# sensor_interface.net
KiCad netlist of a schematic drawn in EAGLE
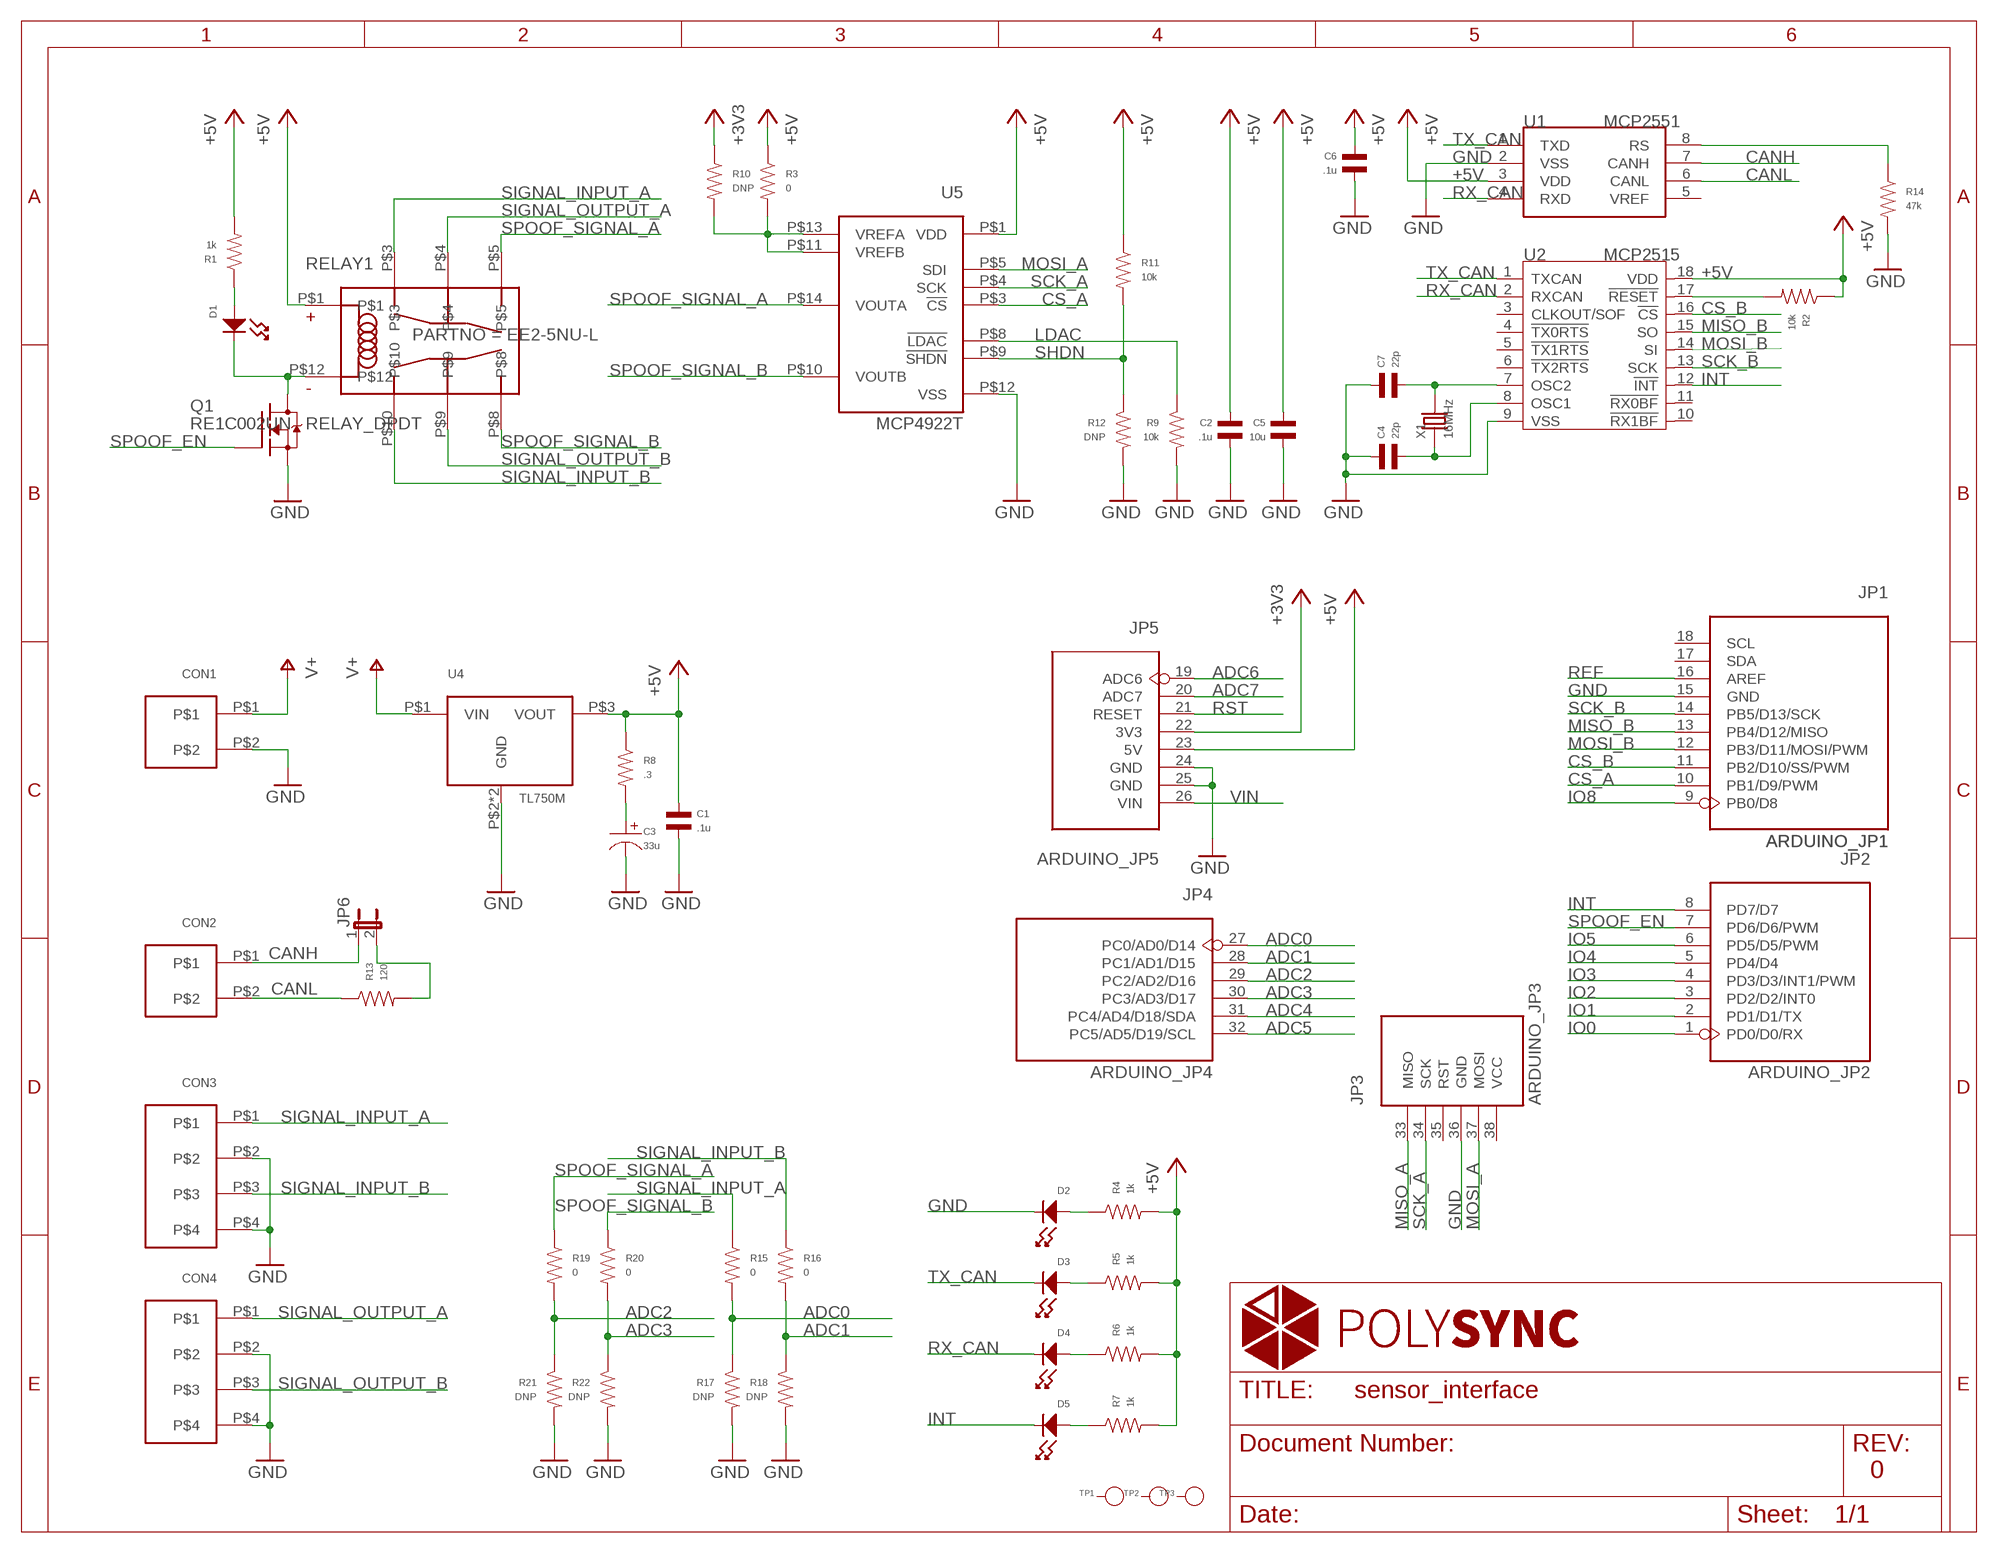
[diagram p0: schematic, sheet 1]

(export (version "E")
  (design (tool "Eeschema 10.0.6"))
  (components
    (comp (ref "C1")
      (value ".1u")
      (footprint "eagle-import:C0402")
      (libsource (lib "eagle-import") (part "CAPACITOR_NP_0402"))
    )
    (comp (ref "C2")
      (value ".1u")
      (footprint "eagle-import:C0402")
      (libsource (lib "eagle-import") (part "CAPACITOR_NP_0402"))
    )
    (comp (ref "C3")
      (value "33u")
      (footprint "eagle-import:CP1206")
      (libsource (lib "eagle-import") (part "CAPACITOR_P"))
    )
    (comp (ref "C4")
      (value "22p")
      (footprint "eagle-import:C0402")
      (libsource (lib "eagle-import") (part "CAPACITOR_NP_0402"))
    )
    (comp (ref "C5")
      (value "10u")
      (footprint "eagle-import:C0805")
      (libsource (lib "eagle-import") (part "CAPACITOR_NP_0805"))
    )
    (comp (ref "C6")
      (value ".1u")
      (footprint "eagle-import:C0402")
      (libsource (lib "eagle-import") (part "CAPACITOR_NP_0402"))
    )
    (comp (ref "C7")
      (value "22p")
      (footprint "eagle-import:C0402")
      (libsource (lib "eagle-import") (part "CAPACITOR_NP_0402"))
    )
    (comp (ref "CON1")
      (value "CON2")
      (footprint "eagle-import:PHOENIX_2_45")
      (libsource (lib "eagle-import") (part "CON2"))
    )
    (comp (ref "CON2")
      (value "CON2")
      (footprint "eagle-import:PHOENIX_2_45")
      (libsource (lib "eagle-import") (part "CON2"))
    )
    (comp (ref "CON3")
      (value "CON4")
      (footprint "eagle-import:PHOENIX_4_45")
      (libsource (lib "eagle-import") (part "CON4"))
    )
    (comp (ref "CON4")
      (value "CON4")
      (footprint "eagle-import:PHOENIX_4_45")
      (libsource (lib "eagle-import") (part "CON4"))
    )
    (comp (ref "D1")
      (value "LED_SINGLE-0603")
      (footprint "eagle-import:LED0603")
      (fields (field (name "HOUSEPART") "NO"))
      (libsource (lib "eagle-import") (part "LED_SINGLE-0603"))
    )
    (comp (ref "D2")
      (value "LED_SINGLE-0603")
      (footprint "eagle-import:LED0603")
      (fields (field (name "HOUSEPART") "NO"))
      (libsource (lib "eagle-import") (part "LED_SINGLE-0603"))
    )
    (comp (ref "D3")
      (value "LED_SINGLE-0603")
      (footprint "eagle-import:LED0603")
      (fields (field (name "HOUSEPART") "NO"))
      (libsource (lib "eagle-import") (part "LED_SINGLE-0603"))
    )
    (comp (ref "D4")
      (value "LED_SINGLE-0603")
      (footprint "eagle-import:LED0603")
      (fields (field (name "HOUSEPART") "NO"))
      (libsource (lib "eagle-import") (part "LED_SINGLE-0603"))
    )
    (comp (ref "D5")
      (value "LED_SINGLE-0603")
      (footprint "eagle-import:LED0603")
      (fields (field (name "HOUSEPART") "NO"))
      (libsource (lib "eagle-import") (part "LED_SINGLE-0603"))
    )
    (comp (ref "JP1")
      (value "ARDUINO_JP1")
      (footprint "eagle-import:ARDUINO_JP1")
      (libsource (lib "eagle-import") (part "ARDUINO_JP1"))
    )
    (comp (ref "JP2")
      (value "ARDUINO_JP2")
      (footprint "eagle-import:ARDUINO_JP2")
      (libsource (lib "eagle-import") (part "ARDUINO_JP2"))
    )
    (comp (ref "JP3")
      (value "ARDUINO_JP3")
      (footprint "eagle-import:ARDUINO_JP3")
      (libsource (lib "eagle-import") (part "ARDUINO_JP3"))
    )
    (comp (ref "JP4")
      (value "ARDUINO_JP4")
      (footprint "eagle-import:ARDUINO_JP4")
      (libsource (lib "eagle-import") (part "ARDUINO_JP4"))
    )
    (comp (ref "JP5")
      (value "ARDUINO_JP5")
      (footprint "eagle-import:ARDUINO_JP5")
      (libsource (lib "eagle-import") (part "ARDUINO_JP5"))
    )
    (comp (ref "JP6")
      (value "JP1E")
      (footprint "eagle-import:JP1")
      (libsource (lib "eagle-import") (part "JP1E"))
    )
    (comp (ref "Q1")
      (value "RE1C002UN")
      (footprint "eagle-import:EMT3F")
      (libsource (lib "eagle-import") (part "RE1C002UN"))
    )
    (comp (ref "R1")
      (value "1k")
      (footprint "eagle-import:R0402")
      (libsource (lib "eagle-import") (part "RESISTOR_0402"))
    )
    (comp (ref "R2")
      (value "10k")
      (footprint "eagle-import:R0402")
      (libsource (lib "eagle-import") (part "RESISTOR_0402"))
    )
    (comp (ref "R3")
      (value "0")
      (footprint "eagle-import:R0402")
      (libsource (lib "eagle-import") (part "RESISTOR_0402"))
    )
    (comp (ref "R4")
      (value "1k")
      (footprint "eagle-import:R0402")
      (libsource (lib "eagle-import") (part "RESISTOR_0402"))
    )
    (comp (ref "R5")
      (value "1k")
      (footprint "eagle-import:R0402")
      (libsource (lib "eagle-import") (part "RESISTOR_0402"))
    )
    (comp (ref "R6")
      (value "1k")
      (footprint "eagle-import:R0402")
      (libsource (lib "eagle-import") (part "RESISTOR_0402"))
    )
    (comp (ref "R7")
      (value "1k")
      (footprint "eagle-import:R0402")
      (libsource (lib "eagle-import") (part "RESISTOR_0402"))
    )
    (comp (ref "R8")
      (value ".3")
      (footprint "eagle-import:R0402")
      (libsource (lib "eagle-import") (part "RESISTOR_0402"))
    )
    (comp (ref "R9")
      (value "10k")
      (footprint "eagle-import:R0402")
      (libsource (lib "eagle-import") (part "RESISTOR_0402"))
    )
    (comp (ref "R10")
      (value "DNP")
      (footprint "eagle-import:R0402")
      (libsource (lib "eagle-import") (part "RESISTOR_0402"))
    )
    (comp (ref "R11")
      (value "10k")
      (footprint "eagle-import:R0402")
      (libsource (lib "eagle-import") (part "RESISTOR_0402"))
    )
    (comp (ref "R12")
      (value "DNP")
      (footprint "eagle-import:R0402")
      (libsource (lib "eagle-import") (part "RESISTOR_0402"))
    )
    (comp (ref "R13")
      (value "120")
      (footprint "eagle-import:R0402")
      (libsource (lib "eagle-import") (part "RESISTOR_0402"))
    )
    (comp (ref "R14")
      (value "47k")
      (footprint "eagle-import:R0402")
      (libsource (lib "eagle-import") (part "RESISTOR_0402"))
    )
    (comp (ref "R15")
      (value "0")
      (footprint "eagle-import:R0402")
      (libsource (lib "eagle-import") (part "RESISTOR_0402"))
    )
    (comp (ref "R16")
      (value "0")
      (footprint "eagle-import:R0402")
      (libsource (lib "eagle-import") (part "RESISTOR_0402"))
    )
    (comp (ref "R17")
      (value "DNP")
      (footprint "eagle-import:R0402")
      (libsource (lib "eagle-import") (part "RESISTOR_0402"))
    )
    (comp (ref "R18")
      (value "DNP")
      (footprint "eagle-import:R0402")
      (libsource (lib "eagle-import") (part "RESISTOR_0402"))
    )
    (comp (ref "R19")
      (value "0")
      (footprint "eagle-import:R0402")
      (libsource (lib "eagle-import") (part "RESISTOR_0402"))
    )
    (comp (ref "R20")
      (value "0")
      (footprint "eagle-import:R0402")
      (libsource (lib "eagle-import") (part "RESISTOR_0402"))
    )
    (comp (ref "R21")
      (value "DNP")
      (footprint "eagle-import:R0402")
      (libsource (lib "eagle-import") (part "RESISTOR_0402"))
    )
    (comp (ref "R22")
      (value "DNP")
      (footprint "eagle-import:R0402")
      (libsource (lib "eagle-import") (part "RESISTOR_0402"))
    )
    (comp (ref "RELAY1")
      (value "RELAY_DPDT")
      (footprint "eagle-import:KEMET_EE2")
      (fields (field (name "PARTNO") "EE2-5NU-L"))
      (libsource (lib "eagle-import") (part "RELAY_DPDT"))
    )
    (comp (ref "TP1")
      (value "PAD-TEST-POINT'4545'")
      (footprint "eagle-import:TP_4545")
      (fields (field (name "PARTNO") "DNP"))
      (libsource (lib "eagle-import") (part "PAD-TEST-POINT'4545'"))
    )
    (comp (ref "TP2")
      (value "PAD-TEST-POINT'4545'")
      (footprint "eagle-import:TP_4545")
      (fields (field (name "PARTNO") "DNP"))
      (libsource (lib "eagle-import") (part "PAD-TEST-POINT'4545'"))
    )
    (comp (ref "TP3")
      (value "PAD-TEST-POINT'4545'")
      (footprint "eagle-import:TP_4545")
      (fields (field (name "PARTNO") "DNP"))
      (libsource (lib "eagle-import") (part "PAD-TEST-POINT'4545'"))
    )
    (comp (ref "U1")
      (value "MCP2551")
      (footprint "eagle-import:SOIC8-6.0")
      (libsource (lib "eagle-import") (part "MCP2551-SOIC8"))
    )
    (comp (ref "U2")
      (value "MCP2515")
      (footprint "eagle-import:SOIC18")
      (libsource (lib "eagle-import") (part "MCP2515-SOIC18"))
    )
    (comp (ref "U4")
      (value "TL750M")
      (footprint "eagle-import:TO-263")
      (libsource (lib "eagle-import") (part "TL750M"))
    )
    (comp (ref "U5")
      (value "MCP4922T")
      (footprint "eagle-import:TSSOP-14")
      (libsource (lib "eagle-import") (part "MCP4922T"))
    )
    (comp (ref "X1")
      (value "16MHz")
      (footprint "eagle-import:HC49UP")
      (libsource (lib "eagle-import") (part "CRYSTAL-HC49UP"))
    )
  )
  (nets
    (net (code "1") (name "+3V3") (class "Default")
      (node (ref "JP5") (pin "22") (pinfunction "3V3_22") (pintype "bidirectional"))
      (node (ref "R10") (pin "P$1") (pinfunction "P$1_P$1") (pintype "passive"))
    )
    (net (code "2") (name "+5V") (class "Default")
      (node (ref "C1") (pin "P$1") (pinfunction "P$1_P$1") (pintype "passive"))
      (node (ref "C2") (pin "P$1") (pinfunction "P$1_P$1") (pintype "passive"))
      (node (ref "C5") (pin "P$1") (pinfunction "P$1_P$1") (pintype "passive"))
      (node (ref "C6") (pin "P$1") (pinfunction "P$1_P$1") (pintype "passive"))
      (node (ref "JP5") (pin "23") (pinfunction "5V_23") (pintype "bidirectional"))
      (node (ref "R1") (pin "P$2") (pinfunction "P$2_P$2") (pintype "passive"))
      (node (ref "R11") (pin "P$1") (pinfunction "P$1_P$1") (pintype "passive"))
      (node (ref "R2") (pin "P$1") (pinfunction "P$1_P$1") (pintype "passive"))
      (node (ref "R3") (pin "P$1") (pinfunction "P$1_P$1") (pintype "passive"))
      (node (ref "R4") (pin "P$2") (pinfunction "P$2_P$2") (pintype "passive"))
      (node (ref "R5") (pin "P$2") (pinfunction "P$2_P$2") (pintype "passive"))
      (node (ref "R6") (pin "P$2") (pinfunction "P$2_P$2") (pintype "passive"))
      (node (ref "R7") (pin "P$2") (pinfunction "P$2_P$2") (pintype "passive"))
      (node (ref "R8") (pin "P$1") (pinfunction "P$1_P$1") (pintype "passive"))
      (node (ref "RELAY1") (pin "P$1") (pinfunction "P$1_P$1") (pintype "bidirectional"))
      (node (ref "U1") (pin "3") (pinfunction "VDD_3") (pintype "bidirectional"))
      (node (ref "U2") (pin "18") (pinfunction "VDD_18") (pintype "power_in"))
      (node (ref "U4") (pin "P$3") (pinfunction "VOUT_P$3") (pintype "bidirectional"))
      (node (ref "U5") (pin "P$1") (pinfunction "VDD_P$1") (pintype "bidirectional"))
    )
    (net (code "3") (name "/ADC0") (class "Default")
      (node (ref "JP4") (pin "27") (pinfunction "PC0/AD0/D14_27") (pintype "bidirectional"))
      (node (ref "R15") (pin "P$2") (pinfunction "P$2_P$2") (pintype "passive"))
      (node (ref "R17") (pin "P$1") (pinfunction "P$1_P$1") (pintype "passive"))
    )
    (net (code "4") (name "/ADC1") (class "Default")
      (node (ref "JP4") (pin "28") (pinfunction "PC1/AD1/D15_28") (pintype "bidirectional"))
      (node (ref "R16") (pin "P$2") (pinfunction "P$2_P$2") (pintype "passive"))
      (node (ref "R18") (pin "P$1") (pinfunction "P$1_P$1") (pintype "passive"))
    )
    (net (code "5") (name "/ADC2") (class "Default")
      (node (ref "JP4") (pin "29") (pinfunction "PC2/AD2/D16_29") (pintype "bidirectional"))
      (node (ref "R19") (pin "P$2") (pinfunction "P$2_P$2") (pintype "passive"))
      (node (ref "R21") (pin "P$1") (pinfunction "P$1_P$1") (pintype "passive"))
    )
    (net (code "6") (name "/ADC3") (class "Default")
      (node (ref "JP4") (pin "30") (pinfunction "PC3/AD3/D17_30") (pintype "bidirectional"))
      (node (ref "R20") (pin "P$2") (pinfunction "P$2_P$2") (pintype "passive"))
      (node (ref "R22") (pin "P$1") (pinfunction "P$1_P$1") (pintype "passive"))
    )
    (net (code "7") (name "/ADC4") (class "Default")
      (node (ref "JP4") (pin "31") (pinfunction "PC4/AD4/D18/SDA_31") (pintype "bidirectional"))
    )
    (net (code "8") (name "/ADC5") (class "Default")
      (node (ref "JP4") (pin "32") (pinfunction "PC5/AD5/D19/SCL_32") (pintype "bidirectional"))
    )
    (net (code "9") (name "/ADC6") (class "Default")
      (node (ref "JP5") (pin "19") (pinfunction "ADC6_19") (pintype "bidirectional"))
    )
    (net (code "10") (name "/ADC7") (class "Default")
      (node (ref "JP5") (pin "20") (pinfunction "ADC7_20") (pintype "bidirectional"))
    )
    (net (code "11") (name "/CANH") (class "Default")
      (node (ref "CON2") (pin "P$1") (pinfunction "P$1_P$1") (pintype "bidirectional"))
      (node (ref "JP6") (pin "1") (pinfunction "1_1") (pintype "passive"))
      (node (ref "U1") (pin "7") (pinfunction "CANH_7") (pintype "bidirectional"))
    )
    (net (code "12") (name "/CANL") (class "Default")
      (node (ref "CON2") (pin "P$2") (pinfunction "P$2_P$2") (pintype "bidirectional"))
      (node (ref "R13") (pin "P$1") (pinfunction "P$1_P$1") (pintype "passive"))
      (node (ref "U1") (pin "6") (pinfunction "CANL_6") (pintype "bidirectional"))
    )
    (net (code "13") (name "/CS_A") (class "Default")
      (node (ref "JP1") (pin "10") (pinfunction "PB1/D9/PWM_10") (pintype "bidirectional"))
      (node (ref "U5") (pin "P$3") (pinfunction "~{CS}_P$3") (pintype "bidirectional"))
    )
    (net (code "14") (name "/CS_B") (class "Default")
      (node (ref "JP1") (pin "11") (pinfunction "PB2/D10/SS/PWM_11") (pintype "bidirectional"))
      (node (ref "U2") (pin "16") (pinfunction "~{CS}_16") (pintype "input"))
    )
    (net (code "15") (name "/INT") (class "Default")
      (node (ref "D5") (pin "CATHODE") (pinfunction "CATHODE_CATHODE") (pintype "power_in"))
      (node (ref "JP2") (pin "8") (pinfunction "PD7/D7_8") (pintype "bidirectional"))
      (node (ref "U2") (pin "12") (pinfunction "~{INT}_12") (pintype "output"))
    )
    (net (code "16") (name "/IO0") (class "Default")
      (node (ref "JP2") (pin "1") (pinfunction "PD0/D0/RX_1") (pintype "bidirectional"))
    )
    (net (code "17") (name "/IO1") (class "Default")
      (node (ref "JP2") (pin "2") (pinfunction "PD1/D1/TX_2") (pintype "bidirectional"))
    )
    (net (code "18") (name "/IO2") (class "Default")
      (node (ref "JP2") (pin "3") (pinfunction "PD2/D2/INT0_3") (pintype "bidirectional"))
    )
    (net (code "19") (name "/IO3") (class "Default")
      (node (ref "JP2") (pin "4") (pinfunction "PD3/D3/INT1/PWM_4") (pintype "bidirectional"))
    )
    (net (code "20") (name "/IO4") (class "Default")
      (node (ref "JP2") (pin "5") (pinfunction "PD4/D4_5") (pintype "bidirectional"))
    )
    (net (code "21") (name "/IO5") (class "Default")
      (node (ref "JP2") (pin "6") (pinfunction "PD5/D5/PWM_6") (pintype "bidirectional"))
    )
    (net (code "22") (name "/IO8") (class "Default")
      (node (ref "JP1") (pin "9") (pinfunction "PB0/D8_9") (pintype "bidirectional"))
    )
    (net (code "23") (name "/LDAC") (class "Default")
      (node (ref "R9") (pin "P$1") (pinfunction "P$1_P$1") (pintype "passive"))
      (node (ref "U5") (pin "P$8") (pinfunction "~{LDAC}_P$8") (pintype "bidirectional"))
    )
    (net (code "24") (name "/MISO_A") (class "Default")
      (node (ref "JP3") (pin "33") (pinfunction "MISO_33") (pintype "bidirectional"))
    )
    (net (code "25") (name "/MISO_B") (class "Default")
      (node (ref "JP1") (pin "13") (pinfunction "PB4/D12/MISO_13") (pintype "bidirectional"))
      (node (ref "U2") (pin "15") (pinfunction "SO_15") (pintype "output"))
    )
    (net (code "26") (name "/MOSI_A") (class "Default")
      (node (ref "JP3") (pin "37") (pinfunction "MOSI_37") (pintype "bidirectional"))
      (node (ref "U5") (pin "P$5") (pinfunction "SDI_P$5") (pintype "bidirectional"))
    )
    (net (code "27") (name "/MOSI_B") (class "Default")
      (node (ref "JP1") (pin "12") (pinfunction "PB3/D11/MOSI/PWM_12") (pintype "bidirectional"))
      (node (ref "U2") (pin "14") (pinfunction "SI_14") (pintype "input"))
    )
    (net (code "28") (name "/REF") (class "Default")
      (node (ref "JP1") (pin "16") (pinfunction "AREF_16") (pintype "bidirectional"))
    )
    (net (code "29") (name "/RST") (class "Default")
      (node (ref "JP5") (pin "21") (pinfunction "RESET_21") (pintype "bidirectional"))
    )
    (net (code "30") (name "/RX_CAN") (class "Default")
      (node (ref "D4") (pin "CATHODE") (pinfunction "CATHODE_CATHODE") (pintype "power_in"))
      (node (ref "U1") (pin "4") (pinfunction "RXD_4") (pintype "bidirectional"))
      (node (ref "U2") (pin "2") (pinfunction "RXCAN_2") (pintype "input"))
    )
    (net (code "31") (name "/SCK_A") (class "Default")
      (node (ref "JP3") (pin "34") (pinfunction "SCK_34") (pintype "bidirectional"))
      (node (ref "U5") (pin "P$4") (pinfunction "SCK_P$4") (pintype "bidirectional"))
    )
    (net (code "32") (name "/SCK_B") (class "Default")
      (node (ref "JP1") (pin "14") (pinfunction "PB5/D13/SCK_14") (pintype "bidirectional"))
      (node (ref "U2") (pin "13") (pinfunction "SCK_13") (pintype "input"))
    )
    (net (code "33") (name "/SHDN") (class "Default")
      (node (ref "R11") (pin "P$2") (pinfunction "P$2_P$2") (pintype "passive"))
      (node (ref "R12") (pin "P$1") (pinfunction "P$1_P$1") (pintype "passive"))
      (node (ref "U5") (pin "P$9") (pinfunction "~{SHDN}_P$9") (pintype "bidirectional"))
    )
    (net (code "34") (name "/SIGNAL_INPUT_A") (class "Default")
      (node (ref "CON3") (pin "P$1") (pinfunction "P$1_P$1") (pintype "bidirectional"))
      (node (ref "R15") (pin "P$1") (pinfunction "P$1_P$1") (pintype "passive"))
      (node (ref "RELAY1") (pin "P$3") (pinfunction "P$3_P$3") (pintype "bidirectional"))
    )
    (net (code "35") (name "/SIGNAL_INPUT_B") (class "Default")
      (node (ref "CON3") (pin "P$3") (pinfunction "P$3_P$3") (pintype "bidirectional"))
      (node (ref "R16") (pin "P$1") (pinfunction "P$1_P$1") (pintype "passive"))
      (node (ref "RELAY1") (pin "P$10") (pinfunction "P$10_P$10") (pintype "bidirectional"))
    )
    (net (code "36") (name "/SIGNAL_OUTPUT_A") (class "Default")
      (node (ref "CON4") (pin "P$1") (pinfunction "P$1_P$1") (pintype "bidirectional"))
      (node (ref "RELAY1") (pin "P$4") (pinfunction "P$4_P$4") (pintype "bidirectional"))
    )
    (net (code "37") (name "/SIGNAL_OUTPUT_B") (class "Default")
      (node (ref "CON4") (pin "P$3") (pinfunction "P$3_P$3") (pintype "bidirectional"))
      (node (ref "RELAY1") (pin "P$9") (pinfunction "P$9_P$9") (pintype "bidirectional"))
    )
    (net (code "38") (name "/SPOOF_EN") (class "Default")
      (node (ref "JP2") (pin "7") (pinfunction "PD6/D6/PWM_7") (pintype "bidirectional"))
      (node (ref "Q1") (pin "P$1") (pinfunction "G_P$1") (pintype "passive"))
    )
    (net (code "39") (name "/SPOOF_SIGNAL_A") (class "Default")
      (node (ref "R19") (pin "P$1") (pinfunction "P$1_P$1") (pintype "passive"))
      (node (ref "RELAY1") (pin "P$5") (pinfunction "P$5_P$5") (pintype "bidirectional"))
      (node (ref "U5") (pin "P$14") (pinfunction "VOUTA_P$14") (pintype "bidirectional"))
    )
    (net (code "40") (name "/SPOOF_SIGNAL_B") (class "Default")
      (node (ref "R20") (pin "P$1") (pinfunction "P$1_P$1") (pintype "passive"))
      (node (ref "RELAY1") (pin "P$8") (pinfunction "P$8_P$8") (pintype "bidirectional"))
      (node (ref "U5") (pin "P$10") (pinfunction "VOUTB_P$10") (pintype "bidirectional"))
    )
    (net (code "41") (name "/TX_CAN") (class "Default")
      (node (ref "D3") (pin "CATHODE") (pinfunction "CATHODE_CATHODE") (pintype "power_in"))
      (node (ref "U1") (pin "1") (pinfunction "TXD_1") (pintype "bidirectional"))
      (node (ref "U2") (pin "1") (pinfunction "TXCAN_1") (pintype "output"))
    )
    (net (code "42") (name "/VIN") (class "Default")
      (node (ref "JP5") (pin "26") (pinfunction "VIN_26") (pintype "bidirectional"))
    )
    (net (code "43") (name "GND") (class "Default")
      (node (ref "C1") (pin "P$2") (pinfunction "P$2_P$2") (pintype "passive"))
      (node (ref "C2") (pin "P$2") (pinfunction "P$2_P$2") (pintype "passive"))
      (node (ref "C3") (pin "P$2") (pinfunction "P$2_P$2") (pintype "passive"))
      (node (ref "C4") (pin "P$1") (pinfunction "P$1_P$1") (pintype "passive"))
      (node (ref "C5") (pin "P$2") (pinfunction "P$2_P$2") (pintype "passive"))
      (node (ref "C6") (pin "P$2") (pinfunction "P$2_P$2") (pintype "passive"))
      (node (ref "C7") (pin "P$1") (pinfunction "P$1_P$1") (pintype "passive"))
      (node (ref "CON1") (pin "P$2") (pinfunction "P$2_P$2") (pintype "bidirectional"))
      (node (ref "CON3") (pin "P$2") (pinfunction "P$2_P$2") (pintype "bidirectional"))
      (node (ref "CON3") (pin "P$4") (pinfunction "P$4_P$4") (pintype "bidirectional"))
      (node (ref "CON4") (pin "P$2") (pinfunction "P$2_P$2") (pintype "bidirectional"))
      (node (ref "CON4") (pin "P$4") (pinfunction "P$4_P$4") (pintype "bidirectional"))
      (node (ref "D2") (pin "CATHODE") (pinfunction "CATHODE_CATHODE") (pintype "power_in"))
      (node (ref "JP1") (pin "15") (pinfunction "GND_15") (pintype "bidirectional"))
      (node (ref "JP3") (pin "36") (pinfunction "GND_36") (pintype "bidirectional"))
      (node (ref "JP5") (pin "24") (pinfunction "GND_24") (pintype "bidirectional"))
      (node (ref "JP5") (pin "25") (pinfunction "GND_25") (pintype "bidirectional"))
      (node (ref "Q1") (pin "P$2") (pinfunction "S_P$2") (pintype "passive"))
      (node (ref "R12") (pin "P$2") (pinfunction "P$2_P$2") (pintype "passive"))
      (node (ref "R14") (pin "P$2") (pinfunction "P$2_P$2") (pintype "passive"))
      (node (ref "R17") (pin "P$2") (pinfunction "P$2_P$2") (pintype "passive"))
      (node (ref "R18") (pin "P$2") (pinfunction "P$2_P$2") (pintype "passive"))
      (node (ref "R21") (pin "P$2") (pinfunction "P$2_P$2") (pintype "passive"))
      (node (ref "R22") (pin "P$2") (pinfunction "P$2_P$2") (pintype "passive"))
      (node (ref "R9") (pin "P$2") (pinfunction "P$2_P$2") (pintype "passive"))
      (node (ref "U1") (pin "2") (pinfunction "VSS_2") (pintype "bidirectional"))
      (node (ref "U2") (pin "9") (pinfunction "VSS_9") (pintype "power_in"))
      (node (ref "U4") (pin "P$2") (pinfunction "GND_P$2") (pintype "bidirectional"))
      (node (ref "U4") (pin "P$4") (pinfunction "GND_P$4") (pintype "bidirectional"))
      (node (ref "U5") (pin "P$12") (pinfunction "VSS_P$12") (pintype "bidirectional"))
    )
    (net (code "44") (name "Net-(C3-PadP$1)") (class "Default")
      (node (ref "C3") (pin "P$1") (pinfunction "P$1_P$1") (pintype "passive"))
      (node (ref "R8") (pin "P$2") (pinfunction "P$2_P$2") (pintype "passive"))
    )
    (net (code "45") (name "Net-(D1-PadANODE)") (class "Default")
      (node (ref "D1") (pin "ANODE") (pinfunction "ANODE_ANODE") (pintype "power_in"))
      (node (ref "R1") (pin "P$1") (pinfunction "P$1_P$1") (pintype "passive"))
    )
    (net (code "46") (name "Net-(D2-PadANODE)") (class "Default")
      (node (ref "D2") (pin "ANODE") (pinfunction "ANODE_ANODE") (pintype "power_in"))
      (node (ref "R4") (pin "P$1") (pinfunction "P$1_P$1") (pintype "passive"))
    )
    (net (code "47") (name "Net-(D3-PadANODE)") (class "Default")
      (node (ref "D3") (pin "ANODE") (pinfunction "ANODE_ANODE") (pintype "power_in"))
      (node (ref "R5") (pin "P$1") (pinfunction "P$1_P$1") (pintype "passive"))
    )
    (net (code "48") (name "Net-(D4-PadANODE)") (class "Default")
      (node (ref "D4") (pin "ANODE") (pinfunction "ANODE_ANODE") (pintype "power_in"))
      (node (ref "R6") (pin "P$1") (pinfunction "P$1_P$1") (pintype "passive"))
    )
    (net (code "49") (name "Net-(D5-PadANODE)") (class "Default")
      (node (ref "D5") (pin "ANODE") (pinfunction "ANODE_ANODE") (pintype "power_in"))
      (node (ref "R7") (pin "P$1") (pinfunction "P$1_P$1") (pintype "passive"))
    )
    (net (code "50") (name "Net-(JP6-Pad2)") (class "Default")
      (node (ref "JP6") (pin "2") (pinfunction "2_2") (pintype "passive"))
      (node (ref "R13") (pin "P$2") (pinfunction "P$2_P$2") (pintype "passive"))
    )
    (net (code "51") (name "Net-(Q1-D)") (class "Default")
      (node (ref "D1") (pin "CATHODE") (pinfunction "CATHODE_CATHODE") (pintype "power_in"))
      (node (ref "Q1") (pin "P$3") (pinfunction "D_P$3") (pintype "passive"))
      (node (ref "RELAY1") (pin "P$12") (pinfunction "P$12_P$12") (pintype "bidirectional"))
    )
    (net (code "52") (name "Net-(U1-RS)") (class "Default")
      (node (ref "R14") (pin "P$1") (pinfunction "P$1_P$1") (pintype "passive"))
      (node (ref "U1") (pin "8") (pinfunction "RS_8") (pintype "bidirectional"))
    )
    (net (code "53") (name "Net-(U2-OSC1)") (class "Default")
      (node (ref "C4") (pin "P$2") (pinfunction "P$2_P$2") (pintype "passive"))
      (node (ref "U2") (pin "8") (pinfunction "OSC1_8") (pintype "input"))
      (node (ref "X1") (pin "1") (pinfunction "1_1") (pintype "passive"))
    )
    (net (code "54") (name "Net-(U2-OSC2)") (class "Default")
      (node (ref "C7") (pin "P$2") (pinfunction "P$2_P$2") (pintype "passive"))
      (node (ref "U2") (pin "7") (pinfunction "OSC2_7") (pintype "output"))
      (node (ref "X1") (pin "2") (pinfunction "2_2") (pintype "passive"))
    )
    (net (code "55") (name "Net-(U2-~{RESET})") (class "Default")
      (node (ref "R2") (pin "P$2") (pinfunction "P$2_P$2") (pintype "passive"))
      (node (ref "U2") (pin "17") (pinfunction "~{RESET}_17") (pintype "input"))
    )
    (net (code "56") (name "Net-(U5-VREFA)") (class "Default")
      (node (ref "R10") (pin "P$2") (pinfunction "P$2_P$2") (pintype "passive"))
      (node (ref "R3") (pin "P$2") (pinfunction "P$2_P$2") (pintype "passive"))
      (node (ref "U5") (pin "P$11") (pinfunction "VREFB_P$11") (pintype "bidirectional"))
      (node (ref "U5") (pin "P$13") (pinfunction "VREFA_P$13") (pintype "bidirectional"))
    )
    (net (code "57") (name "V+") (class "Default")
      (node (ref "CON1") (pin "P$1") (pinfunction "P$1_P$1") (pintype "bidirectional"))
      (node (ref "U4") (pin "P$1") (pinfunction "VIN_P$1") (pintype "bidirectional"))
    )
    (net (code "58") (name "unconnected-(JP1-SCL-Pad18)") (class "Default")
      (node (ref "JP1") (pin "18") (pinfunction "SCL_18") (pintype "bidirectional"))
    )
    (net (code "59") (name "unconnected-(JP1-SDA-Pad17)") (class "Default")
      (node (ref "JP1") (pin "17") (pinfunction "SDA_17") (pintype "bidirectional"))
    )
    (net (code "60") (name "unconnected-(JP3-RST-Pad35)") (class "Default")
      (node (ref "JP3") (pin "35") (pinfunction "RST_35") (pintype "bidirectional"))
    )
    (net (code "61") (name "unconnected-(JP3-VCC-Pad38)") (class "Default")
      (node (ref "JP3") (pin "38") (pinfunction "VCC_38") (pintype "bidirectional"))
    )
    (net (code "62") (name "unconnected-(TP1-PadT)") (class "Default")
      (node (ref "TP1") (pin "T") (pinfunction "T_T") (pintype "bidirectional"))
    )
    (net (code "63") (name "unconnected-(TP2-PadT)") (class "Default")
      (node (ref "TP2") (pin "T") (pinfunction "T_T") (pintype "bidirectional"))
    )
    (net (code "64") (name "unconnected-(TP3-PadT)") (class "Default")
      (node (ref "TP3") (pin "T") (pinfunction "T_T") (pintype "bidirectional"))
    )
    (net (code "65") (name "unconnected-(U1-VREF-Pad5)") (class "Default")
      (node (ref "U1") (pin "5") (pinfunction "VREF_5") (pintype "bidirectional"))
    )
    (net (code "66") (name "unconnected-(U2-CLKOUT{slash}SOF-Pad3)") (class "Default")
      (node (ref "U2") (pin "3") (pinfunction "CLKOUT/SOF_3") (pintype "output"))
    )
    (net (code "67") (name "unconnected-(U2-~{RX0BF}-Pad11)") (class "Default")
      (node (ref "U2") (pin "11") (pinfunction "~{RX0BF}_11") (pintype "output"))
    )
    (net (code "68") (name "unconnected-(U2-~{RX1BF}-Pad10)") (class "Default")
      (node (ref "U2") (pin "10") (pinfunction "~{RX1BF}_10") (pintype "output"))
    )
    (net (code "69") (name "unconnected-(U2-~{TX0RTS}-Pad4)") (class "Default")
      (node (ref "U2") (pin "4") (pinfunction "~{TX0RTS}_4") (pintype "input"))
    )
    (net (code "70") (name "unconnected-(U2-~{TX1RTS}-Pad5)") (class "Default")
      (node (ref "U2") (pin "5") (pinfunction "~{TX1RTS}_5") (pintype "input"))
    )
    (net (code "71") (name "unconnected-(U2-~{TX2RTS}-Pad6)") (class "Default")
      (node (ref "U2") (pin "6") (pinfunction "~{TX2RTS}_6") (pintype "input"))
    )
  )
)
